# minimal_terminal.net
KiCad netlist of a schematic drawn in EAGLE
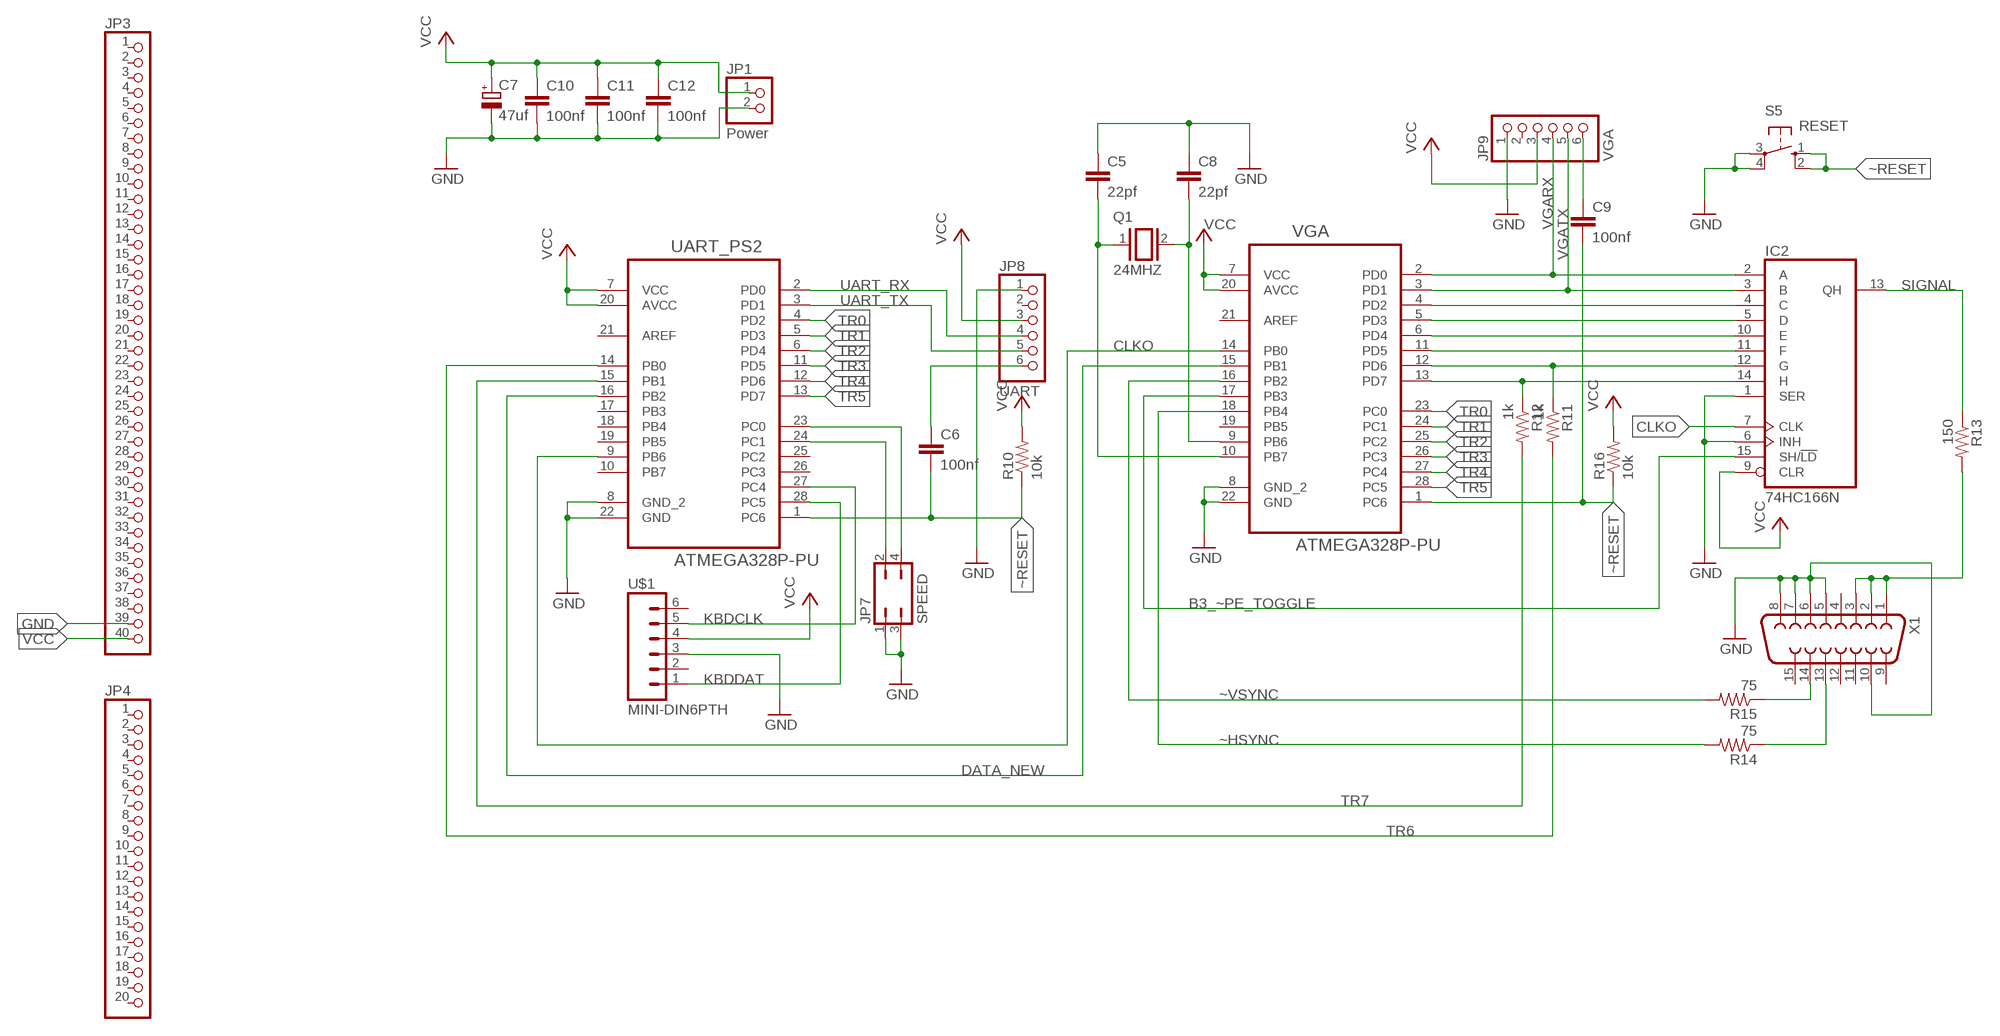
[diagram p0: schematic, sheet 1]

(export (version "E")
  (design (tool "Eeschema 10.0.6"))
  (components
    (comp (ref "C5")
      (value "22pf")
      (footprint "eagle-import:C2.5-3")
      (libsource (lib "eagle-import") (part "C2,5-3"))
    )
    (comp (ref "C6")
      (value "100nf")
      (footprint "eagle-import:C2.5-3")
      (libsource (lib "eagle-import") (part "C2,5-3"))
    )
    (comp (ref "C7")
      (value "47uf")
      (footprint "eagle-import:E2,5-6")
      (libsource (lib "eagle-import") (part "CPOL-EUE2.5-6"))
    )
    (comp (ref "C8")
      (value "22pf")
      (footprint "eagle-import:C2.5-3")
      (libsource (lib "eagle-import") (part "C2,5-3"))
    )
    (comp (ref "C9")
      (value "100nf")
      (footprint "eagle-import:C2.5-3")
      (libsource (lib "eagle-import") (part "C2,5-3"))
    )
    (comp (ref "C10")
      (value "100nf")
      (footprint "eagle-import:C2.5-3")
      (libsource (lib "eagle-import") (part "C2,5-3"))
    )
    (comp (ref "C11")
      (value "100nf")
      (footprint "eagle-import:C2.5-3")
      (libsource (lib "eagle-import") (part "C2,5-3"))
    )
    (comp (ref "C12")
      (value "100nf")
      (footprint "eagle-import:C2.5-3")
      (libsource (lib "eagle-import") (part "C2,5-3"))
    )
    (comp (ref "IC2")
      (value "74HC166N")
      (footprint "eagle-import:DIL16")
      (libsource (lib "eagle-import") (part "74166NHC"))
    )
    (comp (ref "JP1")
      (value "Power")
      (footprint "eagle-import:1X02")
      (libsource (lib "eagle-import") (part "PINHD-1X2"))
    )
    (comp (ref "JP3")
      (value "PINHD-1X40")
      (footprint "eagle-import:1X40")
      (libsource (lib "eagle-import") (part "PINHD-1X40"))
    )
    (comp (ref "JP4")
      (value "PINHD-1X20")
      (footprint "eagle-import:1X20")
      (libsource (lib "eagle-import") (part "PINHD-1X20"))
    )
    (comp (ref "JP7")
      (value "SPEED")
      (footprint "eagle-import:JP2Q")
      (libsource (lib "eagle-import") (part "JP2Q"))
    )
    (comp (ref "JP8")
      (value "UART")
      (footprint "eagle-import:1X06")
      (libsource (lib "eagle-import") (part "PINHD-1X6"))
    )
    (comp (ref "JP9")
      (value "VGA")
      (footprint "eagle-import:1X06")
      (libsource (lib "eagle-import") (part "PINHD-1X6"))
    )
    (comp (ref "Q1")
      (value "24MHZ")
      (footprint "eagle-import:Q")
      (libsource (lib "eagle-import") (part "XTAL"))
    )
    (comp (ref "R10")
      (value "10k")
      (footprint "eagle-import:0204_7")
      (libsource (lib "eagle-import") (part "R-US_0204/7"))
    )
    (comp (ref "R11")
      (value "1k")
      (footprint "eagle-import:0204_7")
      (libsource (lib "eagle-import") (part "R-US_0204/7"))
    )
    (comp (ref "R12")
      (value "1k")
      (footprint "eagle-import:0204_7")
      (libsource (lib "eagle-import") (part "R-US_0204/7"))
    )
    (comp (ref "R13")
      (value "150")
      (footprint "eagle-import:0204_7")
      (libsource (lib "eagle-import") (part "R-US_0204/7"))
    )
    (comp (ref "R14")
      (value "75")
      (footprint "eagle-import:0204_7")
      (libsource (lib "eagle-import") (part "R-US_0204/7"))
    )
    (comp (ref "R15")
      (value "75")
      (footprint "eagle-import:0204_7")
      (libsource (lib "eagle-import") (part "R-US_0204/7"))
    )
    (comp (ref "R16")
      (value "10k")
      (footprint "eagle-import:0204_7")
      (libsource (lib "eagle-import") (part "R-US_0204/7"))
    )
    (comp (ref "S5")
      (value "RESET")
      (footprint "eagle-import:B3F-10XX")
      (fields (field (name "MPN") "B3F-1000"))
      (libsource (lib "eagle-import") (part "10-XX"))
    )
    (comp (ref "U$1")
      (value "MINI-DIN6PTH")
      (footprint "eagle-import:MINI-DIN6")
      (libsource (lib "eagle-import") (part "MINI-DIN6PTH"))
    )
    (comp (ref "UART_PS2")
      (value "ATMEGA328P-PU")
      (footprint "eagle-import:DIP254P762X457-28")
      (libsource (lib "eagle-import") (part "ATMEGA328P-PU"))
    )
    (comp (ref "VGA")
      (value "ATMEGA328P-PU")
      (footprint "eagle-import:DIP254P762X457-28")
      (libsource (lib "eagle-import") (part "ATMEGA328P-PU"))
    )
    (comp (ref "X1")
      (value "F15HDH")
      (footprint "eagle-import:HDF15H")
      (libsource (lib "eagle-import") (part "F15HDH"))
    )
  )
  (nets
    (net (code "1") (name "/B3_~{PE_TOGGLE}") (class "Default")
      (node (ref "IC2") (pin "15") (pinfunction "SH/~{LD}_15") (pintype "input"))
      (node (ref "VGA") (pin "17") (pinfunction "PB3_17") (pintype "bidirectional"))
    )
    (net (code "2") (name "/DATA_NEW") (class "Default")
      (node (ref "UART_PS2") (pin "16") (pinfunction "PB2_16") (pintype "bidirectional"))
      (node (ref "VGA") (pin "15") (pinfunction "PB1_15") (pintype "bidirectional"))
    )
    (net (code "3") (name "/KBDCLK") (class "Default")
      (node (ref "U$1") (pin "5") (pinfunction "5_5") (pintype "passive"))
      (node (ref "UART_PS2") (pin "27") (pinfunction "PC4_27") (pintype "bidirectional"))
    )
    (net (code "4") (name "/KBDDAT") (class "Default")
      (node (ref "U$1") (pin "1") (pinfunction "1_1") (pintype "passive"))
      (node (ref "UART_PS2") (pin "28") (pinfunction "PC5_28") (pintype "bidirectional"))
    )
    (net (code "5") (name "/SIGNAL") (class "Default")
      (node (ref "IC2") (pin "13") (pinfunction "QH_13") (pintype "output"))
      (node (ref "R13") (pin "1") (pinfunction "1_1") (pintype "passive"))
    )
    (net (code "6") (name "/TR6") (class "Default")
      (node (ref "R11") (pin "2") (pinfunction "2_2") (pintype "passive"))
      (node (ref "UART_PS2") (pin "14") (pinfunction "PB0_14") (pintype "bidirectional"))
    )
    (net (code "7") (name "/TR7") (class "Default")
      (node (ref "R12") (pin "2") (pinfunction "2_2") (pintype "passive"))
      (node (ref "UART_PS2") (pin "15") (pinfunction "PB1_15") (pintype "bidirectional"))
    )
    (net (code "8") (name "/UART_RX") (class "Default")
      (node (ref "JP8") (pin "4") (pinfunction "4_4") (pintype "passive"))
      (node (ref "UART_PS2") (pin "2") (pinfunction "PD0_2") (pintype "bidirectional"))
    )
    (net (code "9") (name "/UART_TX") (class "Default")
      (node (ref "JP8") (pin "5") (pinfunction "5_5") (pintype "passive"))
      (node (ref "UART_PS2") (pin "3") (pinfunction "PD1_3") (pintype "bidirectional"))
    )
    (net (code "10") (name "/VGARX") (class "Default")
      (node (ref "IC2") (pin "2") (pinfunction "A_2") (pintype "input"))
      (node (ref "JP9") (pin "4") (pinfunction "4_4") (pintype "passive"))
      (node (ref "VGA") (pin "2") (pinfunction "PD0_2") (pintype "bidirectional"))
    )
    (net (code "11") (name "/VGATX") (class "Default")
      (node (ref "IC2") (pin "3") (pinfunction "B_3") (pintype "input"))
      (node (ref "JP9") (pin "5") (pinfunction "5_5") (pintype "passive"))
      (node (ref "VGA") (pin "3") (pinfunction "PD1_3") (pintype "bidirectional"))
    )
    (net (code "12") (name "/~{HSYNC}") (class "Default")
      (node (ref "R14") (pin "2") (pinfunction "2_2") (pintype "passive"))
      (node (ref "VGA") (pin "18") (pinfunction "PB4_18") (pintype "bidirectional"))
    )
    (net (code "13") (name "/~{RESET}") (class "Default")
      (node (ref "C6") (pin "2") (pinfunction "2_2") (pintype "passive"))
      (node (ref "C9") (pin "2") (pinfunction "2_2") (pintype "passive"))
      (node (ref "R10") (pin "1") (pinfunction "1_1") (pintype "passive"))
      (node (ref "R16") (pin "1") (pinfunction "1_1") (pintype "passive"))
      (node (ref "S5") (pin "1") (pinfunction "S_1") (pintype "passive"))
      (node (ref "S5") (pin "2") (pinfunction "S1_2") (pintype "passive"))
      (node (ref "UART_PS2") (pin "1") (pinfunction "PC6_1") (pintype "bidirectional"))
      (node (ref "VGA") (pin "1") (pinfunction "PC6_1") (pintype "bidirectional"))
    )
    (net (code "14") (name "/~{VSYNC}") (class "Default")
      (node (ref "R15") (pin "2") (pinfunction "2_2") (pintype "passive"))
      (node (ref "VGA") (pin "16") (pinfunction "PB2_16") (pintype "bidirectional"))
    )
    (net (code "15") (name "CLKO") (class "Default")
      (node (ref "IC2") (pin "7") (pinfunction "CLK_7") (pintype "input"))
      (node (ref "UART_PS2") (pin "9") (pinfunction "PB6_9") (pintype "bidirectional"))
      (node (ref "VGA") (pin "14") (pinfunction "PB0_14") (pintype "bidirectional"))
    )
    (net (code "16") (name "GND") (class "Default")
      (node (ref "C10") (pin "2") (pinfunction "2_2") (pintype "passive"))
      (node (ref "C11") (pin "2") (pinfunction "2_2") (pintype "passive"))
      (node (ref "C12") (pin "2") (pinfunction "2_2") (pintype "passive"))
      (node (ref "C5") (pin "1") (pinfunction "1_1") (pintype "passive"))
      (node (ref "C7") (pin "-") (pinfunction "-_-") (pintype "passive"))
      (node (ref "C8") (pin "1") (pinfunction "1_1") (pintype "passive"))
      (node (ref "IC2") (pin "1") (pinfunction "SER_1") (pintype "input"))
      (node (ref "IC2") (pin "6") (pinfunction "INH_6") (pintype "input"))
      (node (ref "JP1") (pin "2") (pinfunction "2_2") (pintype "passive"))
      (node (ref "JP3") (pin "39") (pinfunction "39_39") (pintype "passive"))
      (node (ref "JP7") (pin "1") (pinfunction "1_1") (pintype "passive"))
      (node (ref "JP7") (pin "3") (pinfunction "3_3") (pintype "passive"))
      (node (ref "JP8") (pin "1") (pinfunction "1_1") (pintype "passive"))
      (node (ref "JP9") (pin "1") (pinfunction "1_1") (pintype "passive"))
      (node (ref "S5") (pin "3") (pinfunction "P_3") (pintype "passive"))
      (node (ref "S5") (pin "4") (pinfunction "P1_4") (pintype "passive"))
      (node (ref "U$1") (pin "3") (pinfunction "3_3") (pintype "passive"))
      (node (ref "UART_PS2") (pin "22") (pinfunction "GND_22") (pintype "passive"))
      (node (ref "UART_PS2") (pin "8") (pinfunction "GND_2_8") (pintype "passive"))
      (node (ref "VGA") (pin "22") (pinfunction "GND_22") (pintype "passive"))
      (node (ref "VGA") (pin "8") (pinfunction "GND_2_8") (pintype "passive"))
      (node (ref "X1") (pin "10") (pinfunction "10_10") (pintype "passive"))
      (node (ref "X1") (pin "5") (pinfunction "5_5") (pintype "passive"))
      (node (ref "X1") (pin "6") (pinfunction "6_6") (pintype "passive"))
      (node (ref "X1") (pin "7") (pinfunction "7_7") (pintype "passive"))
      (node (ref "X1") (pin "8") (pinfunction "8_8") (pintype "passive"))
    )
    (net (code "17") (name "Net-(C6-Pad1)") (class "Default")
      (node (ref "C6") (pin "1") (pinfunction "1_1") (pintype "passive"))
      (node (ref "JP8") (pin "6") (pinfunction "6_6") (pintype "passive"))
    )
    (net (code "18") (name "Net-(C9-Pad1)") (class "Default")
      (node (ref "C9") (pin "1") (pinfunction "1_1") (pintype "passive"))
      (node (ref "JP9") (pin "6") (pinfunction "6_6") (pintype "passive"))
    )
    (net (code "19") (name "Net-(IC2A-C)") (class "Default")
      (node (ref "IC2") (pin "4") (pinfunction "C_4") (pintype "input"))
      (node (ref "VGA") (pin "4") (pinfunction "PD2_4") (pintype "bidirectional"))
    )
    (net (code "20") (name "Net-(IC2A-D)") (class "Default")
      (node (ref "IC2") (pin "5") (pinfunction "D_5") (pintype "input"))
      (node (ref "VGA") (pin "5") (pinfunction "PD3_5") (pintype "bidirectional"))
    )
    (net (code "21") (name "Net-(IC2A-E)") (class "Default")
      (node (ref "IC2") (pin "10") (pinfunction "E_10") (pintype "input"))
      (node (ref "VGA") (pin "6") (pinfunction "PD4_6") (pintype "bidirectional"))
    )
    (net (code "22") (name "Net-(IC2A-F)") (class "Default")
      (node (ref "IC2") (pin "11") (pinfunction "F_11") (pintype "input"))
      (node (ref "VGA") (pin "11") (pinfunction "PD5_11") (pintype "bidirectional"))
    )
    (net (code "23") (name "Net-(IC2A-G)") (class "Default")
      (node (ref "IC2") (pin "12") (pinfunction "G_12") (pintype "input"))
      (node (ref "R11") (pin "1") (pinfunction "1_1") (pintype "passive"))
      (node (ref "VGA") (pin "12") (pinfunction "PD6_12") (pintype "bidirectional"))
    )
    (net (code "24") (name "Net-(IC2A-H)") (class "Default")
      (node (ref "IC2") (pin "14") (pinfunction "H_14") (pintype "input"))
      (node (ref "R12") (pin "1") (pinfunction "1_1") (pintype "passive"))
      (node (ref "VGA") (pin "13") (pinfunction "PD7_13") (pintype "bidirectional"))
    )
    (net (code "25") (name "Net-(R13-Pad2)") (class "Default")
      (node (ref "R13") (pin "2") (pinfunction "2_2") (pintype "passive"))
      (node (ref "X1") (pin "1") (pinfunction "1_1") (pintype "passive"))
      (node (ref "X1") (pin "2") (pinfunction "2_2") (pintype "passive"))
      (node (ref "X1") (pin "3") (pinfunction "3_3") (pintype "passive"))
    )
    (net (code "26") (name "Net-(R14-Pad1)") (class "Default")
      (node (ref "R14") (pin "1") (pinfunction "1_1") (pintype "passive"))
      (node (ref "X1") (pin "13") (pinfunction "13_13") (pintype "passive"))
    )
    (net (code "27") (name "Net-(R15-Pad1)") (class "Default")
      (node (ref "R15") (pin "1") (pinfunction "1_1") (pintype "passive"))
      (node (ref "X1") (pin "14") (pinfunction "14_14") (pintype "passive"))
    )
    (net (code "28") (name "Net-(UART_PS2-PC0)") (class "Default")
      (node (ref "JP7") (pin "4") (pinfunction "4_4") (pintype "passive"))
      (node (ref "UART_PS2") (pin "23") (pinfunction "PC0_23") (pintype "bidirectional"))
    )
    (net (code "29") (name "Net-(UART_PS2-PC1)") (class "Default")
      (node (ref "JP7") (pin "2") (pinfunction "2_2") (pintype "passive"))
      (node (ref "UART_PS2") (pin "24") (pinfunction "PC1_24") (pintype "bidirectional"))
    )
    (net (code "30") (name "Net-(VGA-PB6)") (class "Default")
      (node (ref "C8") (pin "2") (pinfunction "2_2") (pintype "passive"))
      (node (ref "Q1") (pin "2") (pinfunction "2_2") (pintype "passive"))
      (node (ref "VGA") (pin "9") (pinfunction "PB6_9") (pintype "bidirectional"))
    )
    (net (code "31") (name "Net-(VGA-PB7)") (class "Default")
      (node (ref "C5") (pin "2") (pinfunction "2_2") (pintype "passive"))
      (node (ref "Q1") (pin "1") (pinfunction "1_1") (pintype "passive"))
      (node (ref "VGA") (pin "10") (pinfunction "PB7_10") (pintype "bidirectional"))
    )
    (net (code "32") (name "TR0") (class "Default")
      (node (ref "UART_PS2") (pin "4") (pinfunction "PD2_4") (pintype "bidirectional"))
      (node (ref "VGA") (pin "23") (pinfunction "PC0_23") (pintype "bidirectional"))
    )
    (net (code "33") (name "TR1") (class "Default")
      (node (ref "UART_PS2") (pin "5") (pinfunction "PD3_5") (pintype "bidirectional"))
      (node (ref "VGA") (pin "24") (pinfunction "PC1_24") (pintype "bidirectional"))
    )
    (net (code "34") (name "TR2") (class "Default")
      (node (ref "UART_PS2") (pin "6") (pinfunction "PD4_6") (pintype "bidirectional"))
      (node (ref "VGA") (pin "25") (pinfunction "PC2_25") (pintype "bidirectional"))
    )
    (net (code "35") (name "TR3") (class "Default")
      (node (ref "UART_PS2") (pin "11") (pinfunction "PD5_11") (pintype "bidirectional"))
      (node (ref "VGA") (pin "26") (pinfunction "PC3_26") (pintype "bidirectional"))
    )
    (net (code "36") (name "TR4") (class "Default")
      (node (ref "UART_PS2") (pin "12") (pinfunction "PD6_12") (pintype "bidirectional"))
      (node (ref "VGA") (pin "27") (pinfunction "PC4_27") (pintype "bidirectional"))
    )
    (net (code "37") (name "TR5") (class "Default")
      (node (ref "UART_PS2") (pin "13") (pinfunction "PD7_13") (pintype "bidirectional"))
      (node (ref "VGA") (pin "28") (pinfunction "PC5_28") (pintype "bidirectional"))
    )
    (net (code "38") (name "VCC") (class "Default")
      (node (ref "C10") (pin "1") (pinfunction "1_1") (pintype "passive"))
      (node (ref "C11") (pin "1") (pinfunction "1_1") (pintype "passive"))
      (node (ref "C12") (pin "1") (pinfunction "1_1") (pintype "passive"))
      (node (ref "C7") (pin "+") (pinfunction "+_+") (pintype "passive"))
      (node (ref "IC2") (pin "9") (pinfunction "CLR_9") (pintype "input"))
      (node (ref "JP1") (pin "1") (pinfunction "1_1") (pintype "passive"))
      (node (ref "JP3") (pin "40") (pinfunction "40_40") (pintype "passive"))
      (node (ref "JP8") (pin "3") (pinfunction "3_3") (pintype "passive"))
      (node (ref "JP9") (pin "3") (pinfunction "3_3") (pintype "passive"))
      (node (ref "R10") (pin "2") (pinfunction "2_2") (pintype "passive"))
      (node (ref "R16") (pin "2") (pinfunction "2_2") (pintype "passive"))
      (node (ref "U$1") (pin "4") (pinfunction "4_4") (pintype "passive"))
      (node (ref "UART_PS2") (pin "20") (pinfunction "AVCC_20") (pintype "power_in"))
      (node (ref "UART_PS2") (pin "7") (pinfunction "VCC_7") (pintype "power_in"))
      (node (ref "VGA") (pin "20") (pinfunction "AVCC_20") (pintype "power_in"))
      (node (ref "VGA") (pin "7") (pinfunction "VCC_7") (pintype "power_in"))
    )
    (net (code "39") (name "unconnected-(JP3-Pad1)") (class "Default")
      (node (ref "JP3") (pin "1") (pinfunction "1_1") (pintype "passive"))
    )
    (net (code "40") (name "unconnected-(JP3-Pad2)") (class "Default")
      (node (ref "JP3") (pin "2") (pinfunction "2_2") (pintype "passive"))
    )
    (net (code "41") (name "unconnected-(JP3-Pad3)") (class "Default")
      (node (ref "JP3") (pin "3") (pinfunction "3_3") (pintype "passive"))
    )
    (net (code "42") (name "unconnected-(JP3-Pad4)") (class "Default")
      (node (ref "JP3") (pin "4") (pinfunction "4_4") (pintype "passive"))
    )
    (net (code "43") (name "unconnected-(JP3-Pad5)") (class "Default")
      (node (ref "JP3") (pin "5") (pinfunction "5_5") (pintype "passive"))
    )
    (net (code "44") (name "unconnected-(JP3-Pad6)") (class "Default")
      (node (ref "JP3") (pin "6") (pinfunction "6_6") (pintype "passive"))
    )
    (net (code "45") (name "unconnected-(JP3-Pad7)") (class "Default")
      (node (ref "JP3") (pin "7") (pinfunction "7_7") (pintype "passive"))
    )
    (net (code "46") (name "unconnected-(JP3-Pad8)") (class "Default")
      (node (ref "JP3") (pin "8") (pinfunction "8_8") (pintype "passive"))
    )
    (net (code "47") (name "unconnected-(JP3-Pad9)") (class "Default")
      (node (ref "JP3") (pin "9") (pinfunction "9_9") (pintype "passive"))
    )
    (net (code "48") (name "unconnected-(JP3-Pad10)") (class "Default")
      (node (ref "JP3") (pin "10") (pinfunction "10_10") (pintype "passive"))
    )
    (net (code "49") (name "unconnected-(JP3-Pad11)") (class "Default")
      (node (ref "JP3") (pin "11") (pinfunction "11_11") (pintype "passive"))
    )
    (net (code "50") (name "unconnected-(JP3-Pad12)") (class "Default")
      (node (ref "JP3") (pin "12") (pinfunction "12_12") (pintype "passive"))
    )
    (net (code "51") (name "unconnected-(JP3-Pad13)") (class "Default")
      (node (ref "JP3") (pin "13") (pinfunction "13_13") (pintype "passive"))
    )
    (net (code "52") (name "unconnected-(JP3-Pad14)") (class "Default")
      (node (ref "JP3") (pin "14") (pinfunction "14_14") (pintype "passive"))
    )
    (net (code "53") (name "unconnected-(JP3-Pad15)") (class "Default")
      (node (ref "JP3") (pin "15") (pinfunction "15_15") (pintype "passive"))
    )
    (net (code "54") (name "unconnected-(JP3-Pad16)") (class "Default")
      (node (ref "JP3") (pin "16") (pinfunction "16_16") (pintype "passive"))
    )
    (net (code "55") (name "unconnected-(JP3-Pad17)") (class "Default")
      (node (ref "JP3") (pin "17") (pinfunction "17_17") (pintype "passive"))
    )
    (net (code "56") (name "unconnected-(JP3-Pad18)") (class "Default")
      (node (ref "JP3") (pin "18") (pinfunction "18_18") (pintype "passive"))
    )
    (net (code "57") (name "unconnected-(JP3-Pad19)") (class "Default")
      (node (ref "JP3") (pin "19") (pinfunction "19_19") (pintype "passive"))
    )
    (net (code "58") (name "unconnected-(JP3-Pad20)") (class "Default")
      (node (ref "JP3") (pin "20") (pinfunction "20_20") (pintype "passive"))
    )
    (net (code "59") (name "unconnected-(JP3-Pad21)") (class "Default")
      (node (ref "JP3") (pin "21") (pinfunction "21_21") (pintype "passive"))
    )
    (net (code "60") (name "unconnected-(JP3-Pad22)") (class "Default")
      (node (ref "JP3") (pin "22") (pinfunction "22_22") (pintype "passive"))
    )
    (net (code "61") (name "unconnected-(JP3-Pad23)") (class "Default")
      (node (ref "JP3") (pin "23") (pinfunction "23_23") (pintype "passive"))
    )
    (net (code "62") (name "unconnected-(JP3-Pad24)") (class "Default")
      (node (ref "JP3") (pin "24") (pinfunction "24_24") (pintype "passive"))
    )
    (net (code "63") (name "unconnected-(JP3-Pad25)") (class "Default")
      (node (ref "JP3") (pin "25") (pinfunction "25_25") (pintype "passive"))
    )
    (net (code "64") (name "unconnected-(JP3-Pad26)") (class "Default")
      (node (ref "JP3") (pin "26") (pinfunction "26_26") (pintype "passive"))
    )
    (net (code "65") (name "unconnected-(JP3-Pad27)") (class "Default")
      (node (ref "JP3") (pin "27") (pinfunction "27_27") (pintype "passive"))
    )
    (net (code "66") (name "unconnected-(JP3-Pad28)") (class "Default")
      (node (ref "JP3") (pin "28") (pinfunction "28_28") (pintype "passive"))
    )
    (net (code "67") (name "unconnected-(JP3-Pad29)") (class "Default")
      (node (ref "JP3") (pin "29") (pinfunction "29_29") (pintype "passive"))
    )
    (net (code "68") (name "unconnected-(JP3-Pad30)") (class "Default")
      (node (ref "JP3") (pin "30") (pinfunction "30_30") (pintype "passive"))
    )
    (net (code "69") (name "unconnected-(JP3-Pad31)") (class "Default")
      (node (ref "JP3") (pin "31") (pinfunction "31_31") (pintype "passive"))
    )
    (net (code "70") (name "unconnected-(JP3-Pad32)") (class "Default")
      (node (ref "JP3") (pin "32") (pinfunction "32_32") (pintype "passive"))
    )
    (net (code "71") (name "unconnected-(JP3-Pad33)") (class "Default")
      (node (ref "JP3") (pin "33") (pinfunction "33_33") (pintype "passive"))
    )
    (net (code "72") (name "unconnected-(JP3-Pad34)") (class "Default")
      (node (ref "JP3") (pin "34") (pinfunction "34_34") (pintype "passive"))
    )
    (net (code "73") (name "unconnected-(JP3-Pad35)") (class "Default")
      (node (ref "JP3") (pin "35") (pinfunction "35_35") (pintype "passive"))
    )
    (net (code "74") (name "unconnected-(JP3-Pad36)") (class "Default")
      (node (ref "JP3") (pin "36") (pinfunction "36_36") (pintype "passive"))
    )
    (net (code "75") (name "unconnected-(JP3-Pad37)") (class "Default")
      (node (ref "JP3") (pin "37") (pinfunction "37_37") (pintype "passive"))
    )
    (net (code "76") (name "unconnected-(JP3-Pad38)") (class "Default")
      (node (ref "JP3") (pin "38") (pinfunction "38_38") (pintype "passive"))
    )
    (net (code "77") (name "unconnected-(JP4-Pad1)") (class "Default")
      (node (ref "JP4") (pin "1") (pinfunction "1_1") (pintype "passive"))
    )
    (net (code "78") (name "unconnected-(JP4-Pad2)") (class "Default")
      (node (ref "JP4") (pin "2") (pinfunction "2_2") (pintype "passive"))
    )
    (net (code "79") (name "unconnected-(JP4-Pad3)") (class "Default")
      (node (ref "JP4") (pin "3") (pinfunction "3_3") (pintype "passive"))
    )
    (net (code "80") (name "unconnected-(JP4-Pad4)") (class "Default")
      (node (ref "JP4") (pin "4") (pinfunction "4_4") (pintype "passive"))
    )
    (net (code "81") (name "unconnected-(JP4-Pad5)") (class "Default")
      (node (ref "JP4") (pin "5") (pinfunction "5_5") (pintype "passive"))
    )
    (net (code "82") (name "unconnected-(JP4-Pad6)") (class "Default")
      (node (ref "JP4") (pin "6") (pinfunction "6_6") (pintype "passive"))
    )
    (net (code "83") (name "unconnected-(JP4-Pad7)") (class "Default")
      (node (ref "JP4") (pin "7") (pinfunction "7_7") (pintype "passive"))
    )
    (net (code "84") (name "unconnected-(JP4-Pad8)") (class "Default")
      (node (ref "JP4") (pin "8") (pinfunction "8_8") (pintype "passive"))
    )
    (net (code "85") (name "unconnected-(JP4-Pad9)") (class "Default")
      (node (ref "JP4") (pin "9") (pinfunction "9_9") (pintype "passive"))
    )
    (net (code "86") (name "unconnected-(JP4-Pad10)") (class "Default")
      (node (ref "JP4") (pin "10") (pinfunction "10_10") (pintype "passive"))
    )
    (net (code "87") (name "unconnected-(JP4-Pad11)") (class "Default")
      (node (ref "JP4") (pin "11") (pinfunction "11_11") (pintype "passive"))
    )
    (net (code "88") (name "unconnected-(JP4-Pad12)") (class "Default")
      (node (ref "JP4") (pin "12") (pinfunction "12_12") (pintype "passive"))
    )
    (net (code "89") (name "unconnected-(JP4-Pad13)") (class "Default")
      (node (ref "JP4") (pin "13") (pinfunction "13_13") (pintype "passive"))
    )
    (net (code "90") (name "unconnected-(JP4-Pad14)") (class "Default")
      (node (ref "JP4") (pin "14") (pinfunction "14_14") (pintype "passive"))
    )
    (net (code "91") (name "unconnected-(JP4-Pad15)") (class "Default")
      (node (ref "JP4") (pin "15") (pinfunction "15_15") (pintype "passive"))
    )
    (net (code "92") (name "unconnected-(JP4-Pad16)") (class "Default")
      (node (ref "JP4") (pin "16") (pinfunction "16_16") (pintype "passive"))
    )
    (net (code "93") (name "unconnected-(JP4-Pad17)") (class "Default")
      (node (ref "JP4") (pin "17") (pinfunction "17_17") (pintype "passive"))
    )
    (net (code "94") (name "unconnected-(JP4-Pad18)") (class "Default")
      (node (ref "JP4") (pin "18") (pinfunction "18_18") (pintype "passive"))
    )
    (net (code "95") (name "unconnected-(JP4-Pad19)") (class "Default")
      (node (ref "JP4") (pin "19") (pinfunction "19_19") (pintype "passive"))
    )
    (net (code "96") (name "unconnected-(JP4-Pad20)") (class "Default")
      (node (ref "JP4") (pin "20") (pinfunction "20_20") (pintype "passive"))
    )
    (net (code "97") (name "unconnected-(JP8-Pad2)") (class "Default")
      (node (ref "JP8") (pin "2") (pinfunction "2_2") (pintype "passive"))
    )
    (net (code "98") (name "unconnected-(JP9-Pad2)") (class "Default")
      (node (ref "JP9") (pin "2") (pinfunction "2_2") (pintype "passive"))
    )
    (net (code "99") (name "unconnected-(U$1-Pad2)") (class "Default")
      (node (ref "U$1") (pin "2") (pinfunction "2_2") (pintype "passive"))
    )
    (net (code "100") (name "unconnected-(U$1-Pad6)") (class "Default")
      (node (ref "U$1") (pin "6") (pinfunction "6_6") (pintype "passive"))
    )
    (net (code "101") (name "unconnected-(UART_PS2-AREF-Pad21)") (class "Default")
      (node (ref "UART_PS2") (pin "21") (pinfunction "AREF_21") (pintype "input"))
    )
    (net (code "102") (name "unconnected-(UART_PS2-PB3-Pad17)") (class "Default")
      (node (ref "UART_PS2") (pin "17") (pinfunction "PB3_17") (pintype "bidirectional"))
    )
    (net (code "103") (name "unconnected-(UART_PS2-PB4-Pad18)") (class "Default")
      (node (ref "UART_PS2") (pin "18") (pinfunction "PB4_18") (pintype "bidirectional"))
    )
    (net (code "104") (name "unconnected-(UART_PS2-PB5-Pad19)") (class "Default")
      (node (ref "UART_PS2") (pin "19") (pinfunction "PB5_19") (pintype "bidirectional"))
    )
    (net (code "105") (name "unconnected-(UART_PS2-PB7-Pad10)") (class "Default")
      (node (ref "UART_PS2") (pin "10") (pinfunction "PB7_10") (pintype "bidirectional"))
    )
    (net (code "106") (name "unconnected-(UART_PS2-PC2-Pad25)") (class "Default")
      (node (ref "UART_PS2") (pin "25") (pinfunction "PC2_25") (pintype "bidirectional"))
    )
    (net (code "107") (name "unconnected-(UART_PS2-PC3-Pad26)") (class "Default")
      (node (ref "UART_PS2") (pin "26") (pinfunction "PC3_26") (pintype "bidirectional"))
    )
    (net (code "108") (name "unconnected-(VGA-AREF-Pad21)") (class "Default")
      (node (ref "VGA") (pin "21") (pinfunction "AREF_21") (pintype "input"))
    )
    (net (code "109") (name "unconnected-(VGA-PB5-Pad19)") (class "Default")
      (node (ref "VGA") (pin "19") (pinfunction "PB5_19") (pintype "bidirectional"))
    )
    (net (code "110") (name "unconnected-(X1-Pad4)") (class "Default")
      (node (ref "X1") (pin "4") (pinfunction "4_4") (pintype "passive"))
    )
    (net (code "111") (name "unconnected-(X1-Pad9)") (class "Default")
      (node (ref "X1") (pin "9") (pinfunction "9_9") (pintype "passive"))
    )
    (net (code "112") (name "unconnected-(X1-Pad11)") (class "Default")
      (node (ref "X1") (pin "11") (pinfunction "11_11") (pintype "passive"))
    )
    (net (code "113") (name "unconnected-(X1-Pad12)") (class "Default")
      (node (ref "X1") (pin "12") (pinfunction "12_12") (pintype "passive"))
    )
    (net (code "114") (name "unconnected-(X1-Pad15)") (class "Default")
      (node (ref "X1") (pin "15") (pinfunction "15_15") (pintype "passive"))
    )
  )
)
